# Stethi.net
KiCad netlist of a schematic drawn in EAGLE
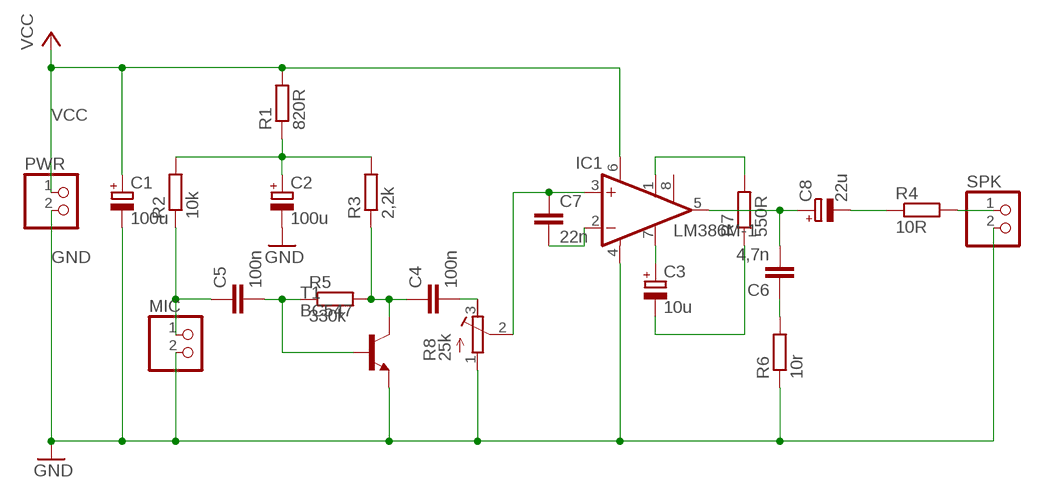
[diagram p0: schematic, sheet 1]

(export (version "E")
  (design (tool "Eeschema 10.0.6"))
  (components
    (comp (ref "C1")
      (value "100u")
      (footprint "eagle-import:A_3216-18W")
      (libsource (lib "eagle-import") (part "CPOL-EUA/3216-18W"))
    )
    (comp (ref "C2")
      (value "100u")
      (footprint "eagle-import:A_3216-18W")
      (libsource (lib "eagle-import") (part "CPOL-EUA/3216-18W"))
    )
    (comp (ref "C3")
      (value "10u")
      (footprint "eagle-import:A_3216-18W")
      (libsource (lib "eagle-import") (part "CPOL-EUA/3216-18W"))
    )
    (comp (ref "C4")
      (value "100n")
      (footprint "eagle-import:C0805K")
      (libsource (lib "eagle-import") (part "C-EUC0805K"))
    )
    (comp (ref "C5")
      (value "100n")
      (footprint "eagle-import:C0805K")
      (libsource (lib "eagle-import") (part "C-EUC0805K"))
    )
    (comp (ref "C6")
      (value "4,7n")
      (footprint "eagle-import:C0805K")
      (libsource (lib "eagle-import") (part "C-EUC0805K"))
    )
    (comp (ref "C7")
      (value "22n")
      (footprint "eagle-import:C0805K")
      (libsource (lib "eagle-import") (part "C-EUC0805K"))
    )
    (comp (ref "C8")
      (value "22u")
      (footprint "eagle-import:A_3216-18W")
      (libsource (lib "eagle-import") (part "CPOL-EUA/3216-18W"))
    )
    (comp (ref "IC1")
      (value "LM386M-1")
      (footprint "eagle-import:SO08")
      (libsource (lib "eagle-import") (part "LM386?-M1"))
    )
    (comp (ref "MIC")
      (value "PINHD-1X2")
      (footprint "eagle-import:1X02")
      (libsource (lib "eagle-import") (part "PINHD-1X2"))
    )
    (comp (ref "PWR")
      (value "PINHD-1X2")
      (footprint "eagle-import:1X02")
      (libsource (lib "eagle-import") (part "PINHD-1X2"))
    )
    (comp (ref "R1")
      (value "820R")
      (footprint "eagle-import:R0805")
      (libsource (lib "eagle-import") (part "R-EU_R0805"))
    )
    (comp (ref "R2")
      (value "10k")
      (footprint "eagle-import:R0805")
      (libsource (lib "eagle-import") (part "R-EU_R0805"))
    )
    (comp (ref "R3")
      (value "2,2k")
      (footprint "eagle-import:R0805")
      (libsource (lib "eagle-import") (part "R-EU_R0805"))
    )
    (comp (ref "R4")
      (value "10R")
      (footprint "eagle-import:R0805")
      (libsource (lib "eagle-import") (part "R-EU_R0805"))
    )
    (comp (ref "R5")
      (value "330k")
      (footprint "eagle-import:R0805")
      (libsource (lib "eagle-import") (part "R-EU_R0805"))
    )
    (comp (ref "R6")
      (value "10r")
      (footprint "eagle-import:R0805")
      (libsource (lib "eagle-import") (part "R-EU_R0805"))
    )
    (comp (ref "R7")
      (value "550R")
      (footprint "eagle-import:R0805")
      (libsource (lib "eagle-import") (part "R-EU_R0805"))
    )
    (comp (ref "R8")
      (value "25k")
      (footprint "eagle-import:RTRIM5X")
      (libsource (lib "eagle-import") (part "R-TRIMM5X"))
    )
    (comp (ref "SPK")
      (value "PINHD-1X2")
      (footprint "eagle-import:1X02")
      (libsource (lib "eagle-import") (part "PINHD-1X2"))
    )
    (comp (ref "T1")
      (value "BC547")
      (footprint "eagle-import:SOT23-BEC")
      (libsource (lib "eagle-import") (part "-NPN-SOT23-BECBC847"))
    )
  )
  (nets
    (net (code "1") (name "GND") (class "Default")
      (node (ref "C1") (pin "-") (pinfunction "-_-") (pintype "passive"))
      (node (ref "C2") (pin "-") (pinfunction "-_-") (pintype "passive"))
      (node (ref "IC1") (pin "4") (pinfunction "GND_4") (pintype "power_in"))
      (node (ref "MIC") (pin "2") (pinfunction "2_2") (pintype "passive"))
      (node (ref "PWR") (pin "2") (pinfunction "2_2") (pintype "passive"))
      (node (ref "R6") (pin "1") (pinfunction "1_1") (pintype "passive"))
      (node (ref "R8") (pin "1") (pinfunction "A_1") (pintype "passive"))
      (node (ref "SPK") (pin "2") (pinfunction "2_2") (pintype "passive"))
      (node (ref "T1") (pin "E") (pinfunction "E_E") (pintype "passive"))
    )
    (net (code "2") (name "Net-(C2-Pad+)") (class "Default")
      (node (ref "C2") (pin "+") (pinfunction "+_+") (pintype "passive"))
      (node (ref "R1") (pin "1") (pinfunction "1_1") (pintype "passive"))
      (node (ref "R2") (pin "2") (pinfunction "2_2") (pintype "passive"))
      (node (ref "R3") (pin "2") (pinfunction "2_2") (pintype "passive"))
    )
    (net (code "3") (name "Net-(C3-Pad-)") (class "Default")
      (node (ref "C3") (pin "-") (pinfunction "-_-") (pintype "passive"))
      (node (ref "R7") (pin "1") (pinfunction "1_1") (pintype "passive"))
    )
    (net (code "4") (name "Net-(C4-Pad1)") (class "Default")
      (node (ref "C4") (pin "1") (pinfunction "1_1") (pintype "passive"))
      (node (ref "R3") (pin "1") (pinfunction "1_1") (pintype "passive"))
      (node (ref "R5") (pin "2") (pinfunction "2_2") (pintype "passive"))
      (node (ref "T1") (pin "C") (pinfunction "C_C") (pintype "passive"))
    )
    (net (code "5") (name "Net-(C5-Pad1)") (class "Default")
      (node (ref "C5") (pin "1") (pinfunction "1_1") (pintype "passive"))
      (node (ref "MIC") (pin "1") (pinfunction "1_1") (pintype "passive"))
      (node (ref "R2") (pin "1") (pinfunction "1_1") (pintype "passive"))
    )
    (net (code "6") (name "Net-(C5-Pad2)") (class "Default")
      (node (ref "C5") (pin "2") (pinfunction "2_2") (pintype "passive"))
      (node (ref "R5") (pin "1") (pinfunction "1_1") (pintype "passive"))
      (node (ref "T1") (pin "B") (pinfunction "B_B") (pintype "passive"))
    )
    (net (code "7") (name "Net-(C6-Pad1)") (class "Default")
      (node (ref "C6") (pin "1") (pinfunction "1_1") (pintype "passive"))
      (node (ref "R6") (pin "2") (pinfunction "2_2") (pintype "passive"))
    )
    (net (code "8") (name "Net-(C8-Pad-)") (class "Default")
      (node (ref "C8") (pin "-") (pinfunction "-_-") (pintype "passive"))
      (node (ref "R4") (pin "1") (pinfunction "1_1") (pintype "passive"))
    )
    (net (code "9") (name "Net-(IC1-+IN)") (class "Default")
      (node (ref "C7") (pin "1") (pinfunction "1_1") (pintype "passive"))
      (node (ref "IC1") (pin "3") (pinfunction "+IN_3") (pintype "input"))
      (node (ref "R8") (pin "2") (pinfunction "S_2") (pintype "passive"))
    )
    (net (code "10") (name "Net-(IC1--IN)") (class "Default")
      (node (ref "C7") (pin "2") (pinfunction "2_2") (pintype "passive"))
      (node (ref "IC1") (pin "2") (pinfunction "-IN_2") (pintype "input"))
    )
    (net (code "11") (name "Net-(IC1-BYPASS)") (class "Default")
      (node (ref "C3") (pin "+") (pinfunction "+_+") (pintype "passive"))
      (node (ref "IC1") (pin "7") (pinfunction "BYPASS_7") (pintype "passive"))
    )
    (net (code "12") (name "Net-(IC1-GAIN-Pad1)") (class "Default")
      (node (ref "IC1") (pin "1") (pinfunction "GAIN_1") (pintype "passive"))
      (node (ref "R7") (pin "2") (pinfunction "2_2") (pintype "passive"))
    )
    (net (code "13") (name "Net-(IC1-OUT)") (class "Default")
      (node (ref "C6") (pin "2") (pinfunction "2_2") (pintype "passive"))
      (node (ref "C8") (pin "+") (pinfunction "+_+") (pintype "passive"))
      (node (ref "IC1") (pin "5") (pinfunction "OUT_5") (pintype "output"))
    )
    (net (code "14") (name "Net-(R4-Pad2)") (class "Default")
      (node (ref "R4") (pin "2") (pinfunction "2_2") (pintype "passive"))
      (node (ref "SPK") (pin "1") (pinfunction "1_1") (pintype "passive"))
    )
    (net (code "15") (name "Net-(R8-E)") (class "Default")
      (node (ref "C4") (pin "2") (pinfunction "2_2") (pintype "passive"))
      (node (ref "R8") (pin "3") (pinfunction "E_3") (pintype "passive"))
    )
    (net (code "16") (name "VCC") (class "Default")
      (node (ref "C1") (pin "+") (pinfunction "+_+") (pintype "passive"))
      (node (ref "IC1") (pin "6") (pinfunction "VS_6") (pintype "power_in"))
      (node (ref "PWR") (pin "1") (pinfunction "1_1") (pintype "passive"))
      (node (ref "R1") (pin "2") (pinfunction "2_2") (pintype "passive"))
    )
    (net (code "17") (name "unconnected-(IC1-GAIN-Pad8)") (class "Default")
      (node (ref "IC1") (pin "8") (pinfunction "GAIN_8") (pintype "passive"))
    )
  )
)
